# Transducer.net
KiCad netlist of a schematic drawn in Altium Designer
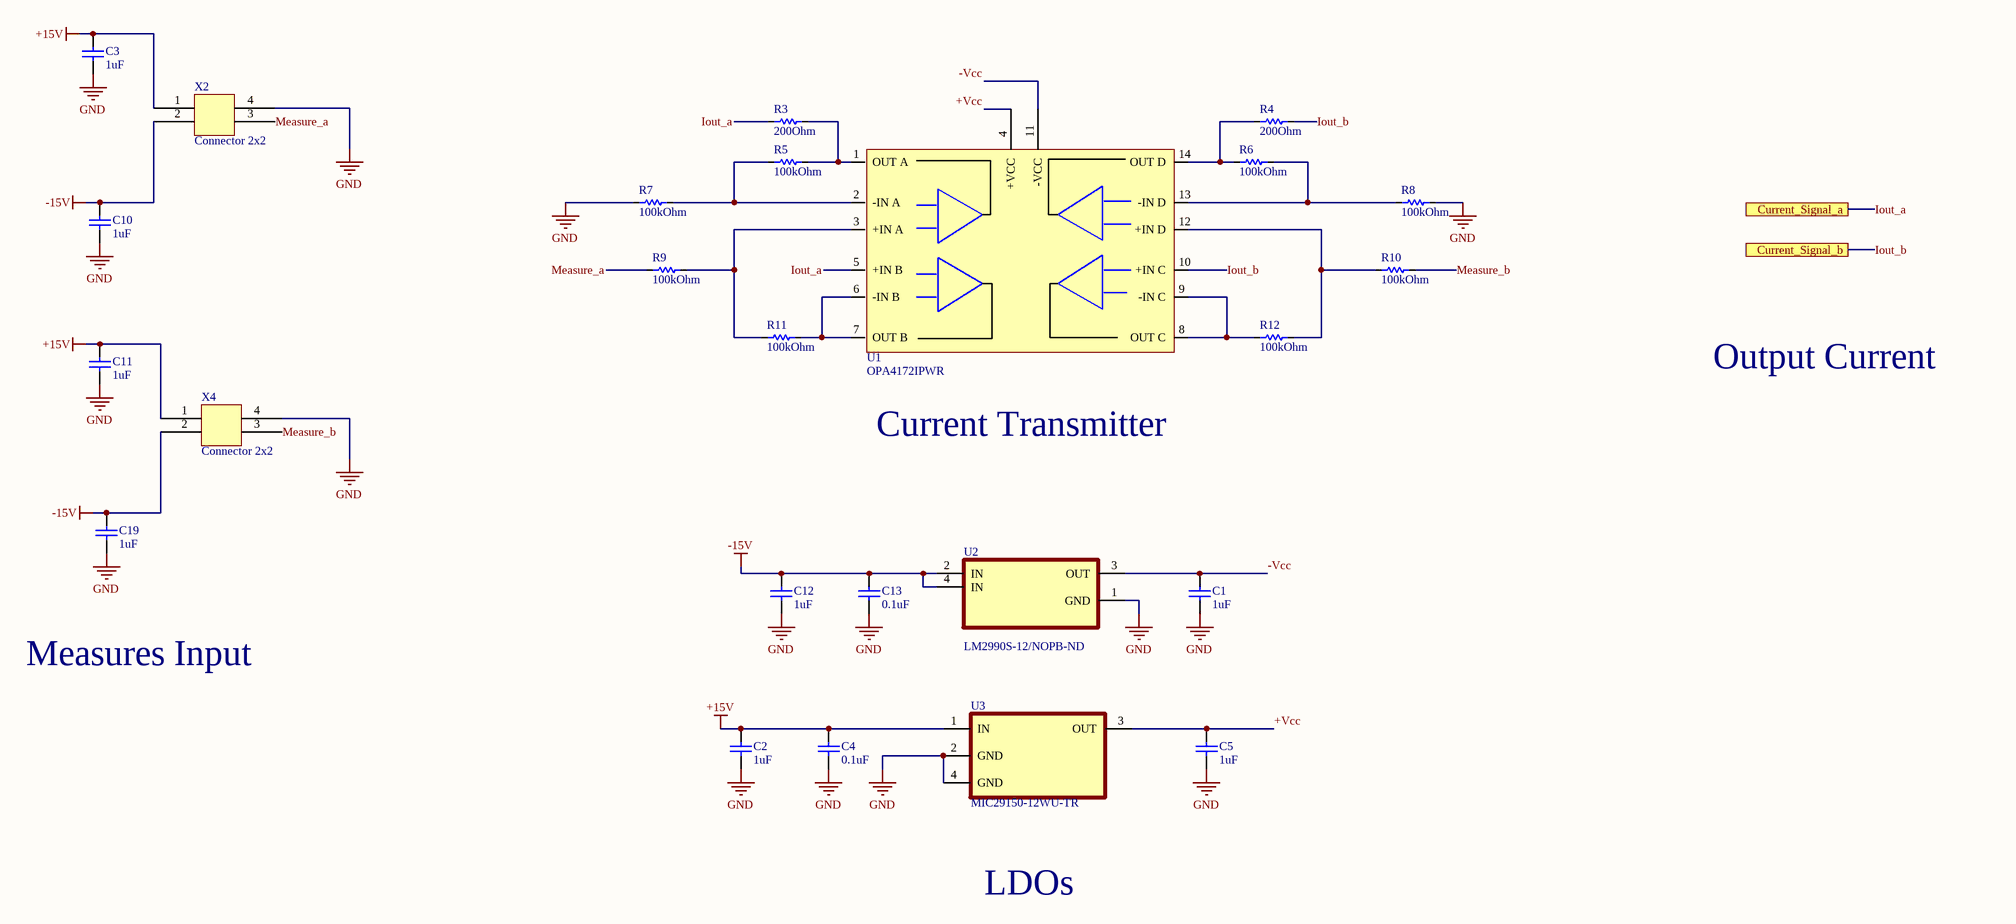
[diagram p0: Transducer.SchDoc]

(export (version "E")
  (design (tool "Eeschema 10.0.6"))
  (components
    (comp (ref "C1")
      (value "1uF")
      (footprint "CAP_1206")
      (description "Cap Ceramic 1uF 35V X7R 20% Pad SMD 1206 125C Low ESR Automotive T/R")
      (fields
        (field (name "MANUFACTURER") "Taiyo Yuden")
        (field (name "MANUFACTURER PART NUMBER") "GMK316B7105MLHT")
      )
      (libsource (lib "Current_SCH_Libraries") (part "GMK316B7105MLHT"))
    )
    (comp (ref "C2")
      (value "1uF")
      (footprint "CAP_1206")
      (description "Cap Ceramic 1uF 35V X7R 20% Pad SMD 1206 125C Low ESR Automotive T/R")
      (fields
        (field (name "MANUFACTURER") "Taiyo Yuden")
        (field (name "MANUFACTURER PART NUMBER") "GMK316B7105MLHT")
      )
      (libsource (lib "Current_SCH_Libraries") (part "GMK316B7105MLHT"))
    )
    (comp (ref "C3")
      (value "1uF")
      (footprint "CAP_1206")
      (description "Cap Ceramic 1uF 35V X7R 20% Pad SMD 1206 125C Low ESR Automotive T/R")
      (fields
        (field (name "MANUFACTURER") "Taiyo Yuden")
        (field (name "MANUFACTURER PART NUMBER") "GMK316B7105MLHT")
      )
      (libsource (lib "Current_SCH_Libraries") (part "GMK316B7105MLHT"))
    )
    (comp (ref "C4")
      (value "0.1uF")
      (footprint "CAP_0603")
      (description "Cap Ceramic 0.1uF 50V X5R 10% SMD 0603 85C T/R")
      (fields
        (field (name "MANUFACTURER") "TDK")
        (field (name "MANUFACTURER PART NUMBER") "C1608X5R1H104K080AA")
      )
      (libsource (lib "Current_SCH_Libraries") (part "C1608X5R1H104K080AA"))
    )
    (comp (ref "C5")
      (value "1uF")
      (footprint "CAP_1206")
      (description "Cap Ceramic 1uF 35V X7R 20% Pad SMD 1206 125C Low ESR Automotive T/R")
      (fields
        (field (name "MANUFACTURER") "Taiyo Yuden")
        (field (name "MANUFACTURER PART NUMBER") "GMK316B7105MLHT")
      )
      (libsource (lib "Current_SCH_Libraries") (part "GMK316B7105MLHT"))
    )
    (comp (ref "C10")
      (value "1uF")
      (footprint "CAP_1206")
      (description "Cap Ceramic 1uF 35V X7R 20% Pad SMD 1206 125C Low ESR Automotive T/R")
      (fields
        (field (name "MANUFACTURER") "Taiyo Yuden")
        (field (name "MANUFACTURER PART NUMBER") "GMK316B7105MLHT")
      )
      (libsource (lib "Current_SCH_Libraries") (part "GMK316B7105MLHT"))
    )
    (comp (ref "C11")
      (value "1uF")
      (footprint "CAP_1206")
      (description "Cap Ceramic 1uF 35V X7R 20% Pad SMD 1206 125C Low ESR Automotive T/R")
      (fields
        (field (name "MANUFACTURER") "Taiyo Yuden")
        (field (name "MANUFACTURER PART NUMBER") "GMK316B7105MLHT")
      )
      (libsource (lib "Current_SCH_Libraries") (part "GMK316B7105MLHT"))
    )
    (comp (ref "C12")
      (value "1uF")
      (footprint "CAP_1206")
      (description "Cap Ceramic 1uF 35V X7R 20% Pad SMD 1206 125C Low ESR Automotive T/R")
      (fields
        (field (name "MANUFACTURER") "Taiyo Yuden")
        (field (name "MANUFACTURER PART NUMBER") "GMK316B7105MLHT")
      )
      (libsource (lib "Current_SCH_Libraries") (part "GMK316B7105MLHT"))
    )
    (comp (ref "C13")
      (value "0.1uF")
      (footprint "CAP_0603")
      (description "Cap Ceramic 0.1uF 50V X5R 10% SMD 0603 85C T/R")
      (fields
        (field (name "MANUFACTURER") "TDK")
        (field (name "MANUFACTURER PART NUMBER") "C1608X5R1H104K080AA")
      )
      (libsource (lib "Current_SCH_Libraries") (part "C1608X5R1H104K080AA"))
    )
    (comp (ref "C19")
      (value "1uF")
      (footprint "CAP_1206")
      (description "Cap Ceramic 1uF 35V X7R 20% Pad SMD 1206 125C Low ESR Automotive T/R")
      (fields
        (field (name "MANUFACTURER") "Taiyo Yuden")
        (field (name "MANUFACTURER PART NUMBER") "GMK316B7105MLHT")
      )
      (libsource (lib "Current_SCH_Libraries") (part "GMK316B7105MLHT"))
    )
    (comp (ref "R3")
      (value "200Ohm")
      (footprint "CAP_1206")
      (description "Res Thin Film 1206 200 Ohm 0.1% 1/4W ±25ppm/°C Molded SMD SMD Punched Carrier T/R")
      (fields
        (field (name "MANUFACTURER") "Panasonic")
        (field (name "MANUFACTURER PART NUMBER") "ERA8AEB201V")
      )
      (libsource (lib "Current_SCH_Libraries") (part "ERA8AEB201V"))
    )
    (comp (ref "R4")
      (value "200Ohm")
      (footprint "CAP_1206")
      (description "Res Thin Film 1206 200 Ohm 0.1% 1/4W ±25ppm/°C Molded SMD SMD Punched Carrier T/R")
      (fields
        (field (name "MANUFACTURER") "Panasonic")
        (field (name "MANUFACTURER PART NUMBER") "ERA8AEB201V")
      )
      (libsource (lib "Current_SCH_Libraries") (part "ERA8AEB201V"))
    )
    (comp (ref "R5")
      (value "100kOhm")
      (footprint "CAP_1206")
      (description "Chip Resistor Automotive Grade Thin Film 1206 100kOhm 0.1% Paper T/R")
      (fields
        (field (name "MANUFACTURER") "Yageo")
        (field (name "MANUFACTURER PART NUMBER") "AT1206BRD07100KL")
      )
      (libsource (lib "Current_SCH_Libraries") (part "AT1206BRD07100KL"))
    )
    (comp (ref "R6")
      (value "100kOhm")
      (footprint "CAP_1206")
      (description "Chip Resistor Automotive Grade Thin Film 1206 100kOhm 0.1% Paper T/R")
      (fields
        (field (name "MANUFACTURER") "Yageo")
        (field (name "MANUFACTURER PART NUMBER") "AT1206BRD07100KL")
      )
      (libsource (lib "Current_SCH_Libraries") (part "AT1206BRD07100KL"))
    )
    (comp (ref "R7")
      (value "100kOhm")
      (footprint "CAP_1206")
      (description "Chip Resistor Automotive Grade Thin Film 1206 100kOhm 0.1% Paper T/R")
      (fields
        (field (name "MANUFACTURER") "Yageo")
        (field (name "MANUFACTURER PART NUMBER") "AT1206BRD07100KL")
      )
      (libsource (lib "Current_SCH_Libraries") (part "AT1206BRD07100KL"))
    )
    (comp (ref "R8")
      (value "100kOhm")
      (footprint "CAP_1206")
      (description "Chip Resistor Automotive Grade Thin Film 1206 100kOhm 0.1% Paper T/R")
      (fields
        (field (name "MANUFACTURER") "Yageo")
        (field (name "MANUFACTURER PART NUMBER") "AT1206BRD07100KL")
      )
      (libsource (lib "Current_SCH_Libraries") (part "AT1206BRD07100KL"))
    )
    (comp (ref "R9")
      (value "100kOhm")
      (footprint "CAP_1206")
      (description "Chip Resistor Automotive Grade Thin Film 1206 100kOhm 0.1% Paper T/R")
      (fields
        (field (name "MANUFACTURER") "Yageo")
        (field (name "MANUFACTURER PART NUMBER") "AT1206BRD07100KL")
      )
      (libsource (lib "Current_SCH_Libraries") (part "AT1206BRD07100KL"))
    )
    (comp (ref "R10")
      (value "100kOhm")
      (footprint "CAP_1206")
      (description "Chip Resistor Automotive Grade Thin Film 1206 100kOhm 0.1% Paper T/R")
      (fields
        (field (name "MANUFACTURER") "Yageo")
        (field (name "MANUFACTURER PART NUMBER") "AT1206BRD07100KL")
      )
      (libsource (lib "Current_SCH_Libraries") (part "AT1206BRD07100KL"))
    )
    (comp (ref "R11")
      (value "100kOhm")
      (footprint "CAP_1206")
      (description "Chip Resistor Automotive Grade Thin Film 1206 100kOhm 0.1% Paper T/R")
      (fields
        (field (name "MANUFACTURER") "Yageo")
        (field (name "MANUFACTURER PART NUMBER") "AT1206BRD07100KL")
      )
      (libsource (lib "Current_SCH_Libraries") (part "AT1206BRD07100KL"))
    )
    (comp (ref "R12")
      (value "100kOhm")
      (footprint "CAP_1206")
      (description "Chip Resistor Automotive Grade Thin Film 1206 100kOhm 0.1% Paper T/R")
      (fields
        (field (name "MANUFACTURER") "Yageo")
        (field (name "MANUFACTURER PART NUMBER") "AT1206BRD07100KL")
      )
      (libsource (lib "Current_SCH_Libraries") (part "AT1206BRD07100KL"))
    )
    (comp (ref "U1")
      (value "OPA4172IPWR")
      (footprint "OPAx172")
      (description "4-Channel, 10-MHz, 36V, high slew-rate, low-noise, RRO, op amp 14-TSSOP -40 to 125")
      (fields (field (name "MANUFACTURER") "Texas Instruments"))
      (libsource (lib "Current_SCH_Libraries") (part "OPA4172IPWR"))
    )
    (comp (ref "U2")
      (value "LM2990S-12/NOPB")
      (footprint "LM2990")
      (description "1-A, negative low-dropout voltage regulator 3-DDPAK/TO-263 -40 to 125")
      (fields
        (field (name "MANUFACTURER") "TI National Semiconductor")
        (field (name "SUPPLIER PART NUMBER 1") "LM2990S-12/NOPB-ND")
      )
      (libsource (lib "Current_SCH_Libraries") (part "LM2990S-12/NOPB"))
    )
    (comp (ref "U3")
      (value "MIC29150-12WU-TR")
      (footprint "MIC29150")
      (description "LDO Regulator Pos 12V 1.5A Automotive 4-Pin(3+Tab) TO-263 T/R")
      (fields (field (name "MANUFACTURER") "Microchip"))
      (libsource (lib "Current_SCH_Libraries") (part "MIC29150-12WU-TR"))
    )
    (comp (ref "X2")
      (value "Connector 2x2")
      (footprint "0039310047")
      (fields (field (name "MANUFACTURER") "Molex") (field (name "MANUFACTURER PART NUMBER") "0039310047"))
      (libsource (lib "Current_SCH_Libraries") (part "0039310047"))
    )
    (comp (ref "X4")
      (value "Connector 2x2")
      (footprint "0039310047")
      (fields (field (name "MANUFACTURER") "Molex") (field (name "MANUFACTURER PART NUMBER") "0039310047"))
      (libsource (lib "Current_SCH_Libraries") (part "0039310047"))
    )
  )
  (nets
    (net (code "1") (name "+15V") (class "Default")
      (node (ref "C11") (pin "1") (pinfunction "1_1") (pintype "passive"))
      (node (ref "C2") (pin "1") (pinfunction "1_1") (pintype "passive"))
      (node (ref "C3") (pin "1") (pinfunction "1_1") (pintype "passive"))
      (node (ref "C4") (pin "1") (pinfunction "1_1") (pintype "passive"))
      (node (ref "U3") (pin "1") (pinfunction "IN_1") (pintype "power_in"))
      (node (ref "X2") (pin "1") (pintype "passive"))
      (node (ref "X4") (pin "1") (pintype "passive"))
    )
    (net (code "2") (name "-15V") (class "Default")
      (node (ref "C10") (pin "1") (pinfunction "1_1") (pintype "passive"))
      (node (ref "C12") (pin "1") (pinfunction "1_1") (pintype "passive"))
      (node (ref "C13") (pin "1") (pinfunction "1_1") (pintype "passive"))
      (node (ref "C19") (pin "1") (pinfunction "1_1") (pintype "passive"))
      (node (ref "U2") (pin "2") (pinfunction "IN_2") (pintype "passive"))
      (node (ref "U2") (pin "4") (pinfunction "IN_4") (pintype "passive"))
      (node (ref "X2") (pin "2") (pintype "passive"))
      (node (ref "X4") (pin "2") (pintype "passive"))
    )
    (net (code "3") (name "/+Vcc") (class "Default")
      (node (ref "C5") (pin "1") (pinfunction "1_1") (pintype "passive"))
      (node (ref "U1") (pin "4") (pinfunction "+VCC_4") (pintype "passive"))
      (node (ref "U3") (pin "3") (pinfunction "OUT_3") (pintype "passive"))
    )
    (net (code "4") (name "/-Vcc") (class "Default")
      (node (ref "C1") (pin "1") (pinfunction "1_1") (pintype "passive"))
      (node (ref "U1") (pin "11") (pinfunction "-VCC_11") (pintype "passive"))
      (node (ref "U2") (pin "3") (pinfunction "OUT_3") (pintype "passive"))
    )
    (net (code "5") (name "/Iout_a") (class "Default")
      (node (ref "R3") (pin "2") (pinfunction "2_2") (pintype "passive"))
      (node (ref "U1") (pin "5") (pinfunction "+IN_B_5") (pintype "passive"))
    )
    (net (code "6") (name "/Iout_b") (class "Default")
      (node (ref "R4") (pin "1") (pinfunction "1_1") (pintype "passive"))
      (node (ref "U1") (pin "10") (pinfunction "+IN_C_10") (pintype "passive"))
    )
    (net (code "7") (name "/Measure_a") (class "Default")
      (node (ref "R9") (pin "2") (pinfunction "2_2") (pintype "passive"))
      (node (ref "X2") (pin "3") (pintype "passive"))
    )
    (net (code "8") (name "/Measure_b") (class "Default")
      (node (ref "R10") (pin "1") (pinfunction "1_1") (pintype "passive"))
      (node (ref "X4") (pin "3") (pintype "passive"))
    )
    (net (code "9") (name "GND") (class "Default")
      (node (ref "C1") (pin "2") (pinfunction "2_2") (pintype "passive"))
      (node (ref "C10") (pin "2") (pinfunction "2_2") (pintype "passive"))
      (node (ref "C11") (pin "2") (pinfunction "2_2") (pintype "passive"))
      (node (ref "C12") (pin "2") (pinfunction "2_2") (pintype "passive"))
      (node (ref "C13") (pin "2") (pinfunction "2_2") (pintype "passive"))
      (node (ref "C19") (pin "2") (pinfunction "2_2") (pintype "passive"))
      (node (ref "C2") (pin "2") (pinfunction "2_2") (pintype "passive"))
      (node (ref "C3") (pin "2") (pinfunction "2_2") (pintype "passive"))
      (node (ref "C4") (pin "2") (pinfunction "2_2") (pintype "passive"))
      (node (ref "C5") (pin "2") (pinfunction "2_2") (pintype "passive"))
      (node (ref "R7") (pin "2") (pinfunction "2_2") (pintype "passive"))
      (node (ref "R8") (pin "1") (pinfunction "1_1") (pintype "passive"))
      (node (ref "U2") (pin "1") (pinfunction "GND_1") (pintype "power_in"))
      (node (ref "U3") (pin "2") (pinfunction "GND_2") (pintype "passive"))
      (node (ref "U3") (pin "4") (pinfunction "GND_4") (pintype "passive"))
      (node (ref "X2") (pin "4") (pintype "passive"))
      (node (ref "X4") (pin "4") (pintype "passive"))
    )
    (net (code "10") (name "Net-(U1-+IN_A)") (class "Default")
      (node (ref "R11") (pin "2") (pinfunction "2_2") (pintype "passive"))
      (node (ref "R9") (pin "1") (pinfunction "1_1") (pintype "passive"))
      (node (ref "U1") (pin "3") (pinfunction "+IN_A_3") (pintype "passive"))
    )
    (net (code "11") (name "Net-(U1-+IN_D)") (class "Default")
      (node (ref "R10") (pin "2") (pinfunction "2_2") (pintype "passive"))
      (node (ref "R12") (pin "1") (pinfunction "1_1") (pintype "passive"))
      (node (ref "U1") (pin "12") (pinfunction "+IN_D_12") (pintype "passive"))
    )
    (net (code "12") (name "Net-(U1--IN_A)") (class "Default")
      (node (ref "R5") (pin "2") (pinfunction "2_2") (pintype "passive"))
      (node (ref "R7") (pin "1") (pinfunction "1_1") (pintype "passive"))
      (node (ref "U1") (pin "2") (pinfunction "-IN_A_2") (pintype "passive"))
    )
    (net (code "13") (name "Net-(U1--IN_B)") (class "Default")
      (node (ref "R11") (pin "1") (pinfunction "1_1") (pintype "passive"))
      (node (ref "U1") (pin "6") (pinfunction "-IN_B_6") (pintype "passive"))
      (node (ref "U1") (pin "7") (pinfunction "OUT_B_7") (pintype "passive"))
    )
    (net (code "14") (name "Net-(U1--IN_C)") (class "Default")
      (node (ref "R12") (pin "2") (pinfunction "2_2") (pintype "passive"))
      (node (ref "U1") (pin "8") (pinfunction "OUT_C_8") (pintype "passive"))
      (node (ref "U1") (pin "9") (pinfunction "-IN_C_9") (pintype "passive"))
    )
    (net (code "15") (name "Net-(U1--IN_D)") (class "Default")
      (node (ref "R6") (pin "1") (pinfunction "1_1") (pintype "passive"))
      (node (ref "R8") (pin "2") (pinfunction "2_2") (pintype "passive"))
      (node (ref "U1") (pin "13") (pinfunction "-IN_D_13") (pintype "passive"))
    )
    (net (code "16") (name "Net-(U1-OUT_A)") (class "Default")
      (node (ref "R3") (pin "1") (pinfunction "1_1") (pintype "passive"))
      (node (ref "R5") (pin "1") (pinfunction "1_1") (pintype "passive"))
      (node (ref "U1") (pin "1") (pinfunction "OUT_A_1") (pintype "passive"))
    )
    (net (code "17") (name "Net-(U1-OUT_D)") (class "Default")
      (node (ref "R4") (pin "2") (pinfunction "2_2") (pintype "passive"))
      (node (ref "R6") (pin "2") (pinfunction "2_2") (pintype "passive"))
      (node (ref "U1") (pin "14") (pinfunction "OUT_D_14") (pintype "passive"))
    )
  )
)
